# Test_Bench.net
KiCad netlist of a schematic drawn in EAGLE
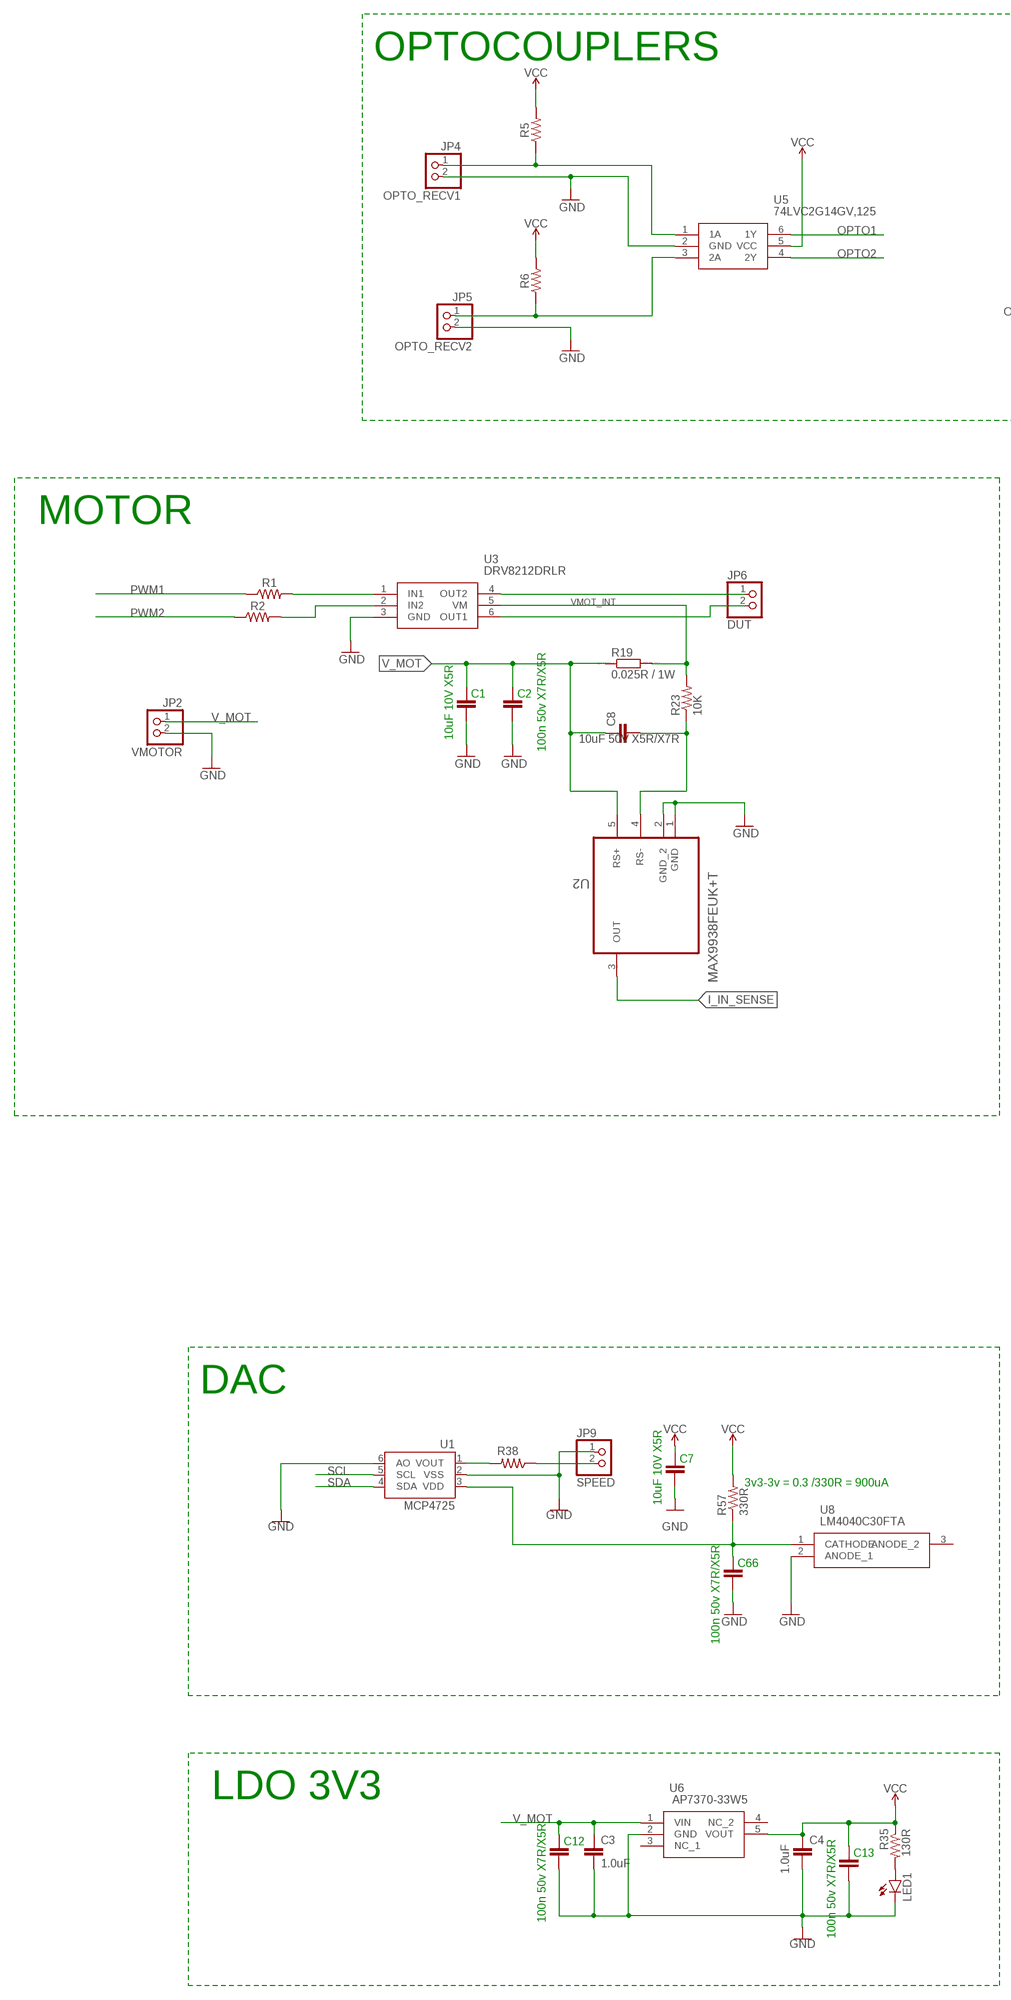
[diagram p0: schematic, sheet 1, part 1 of 2]
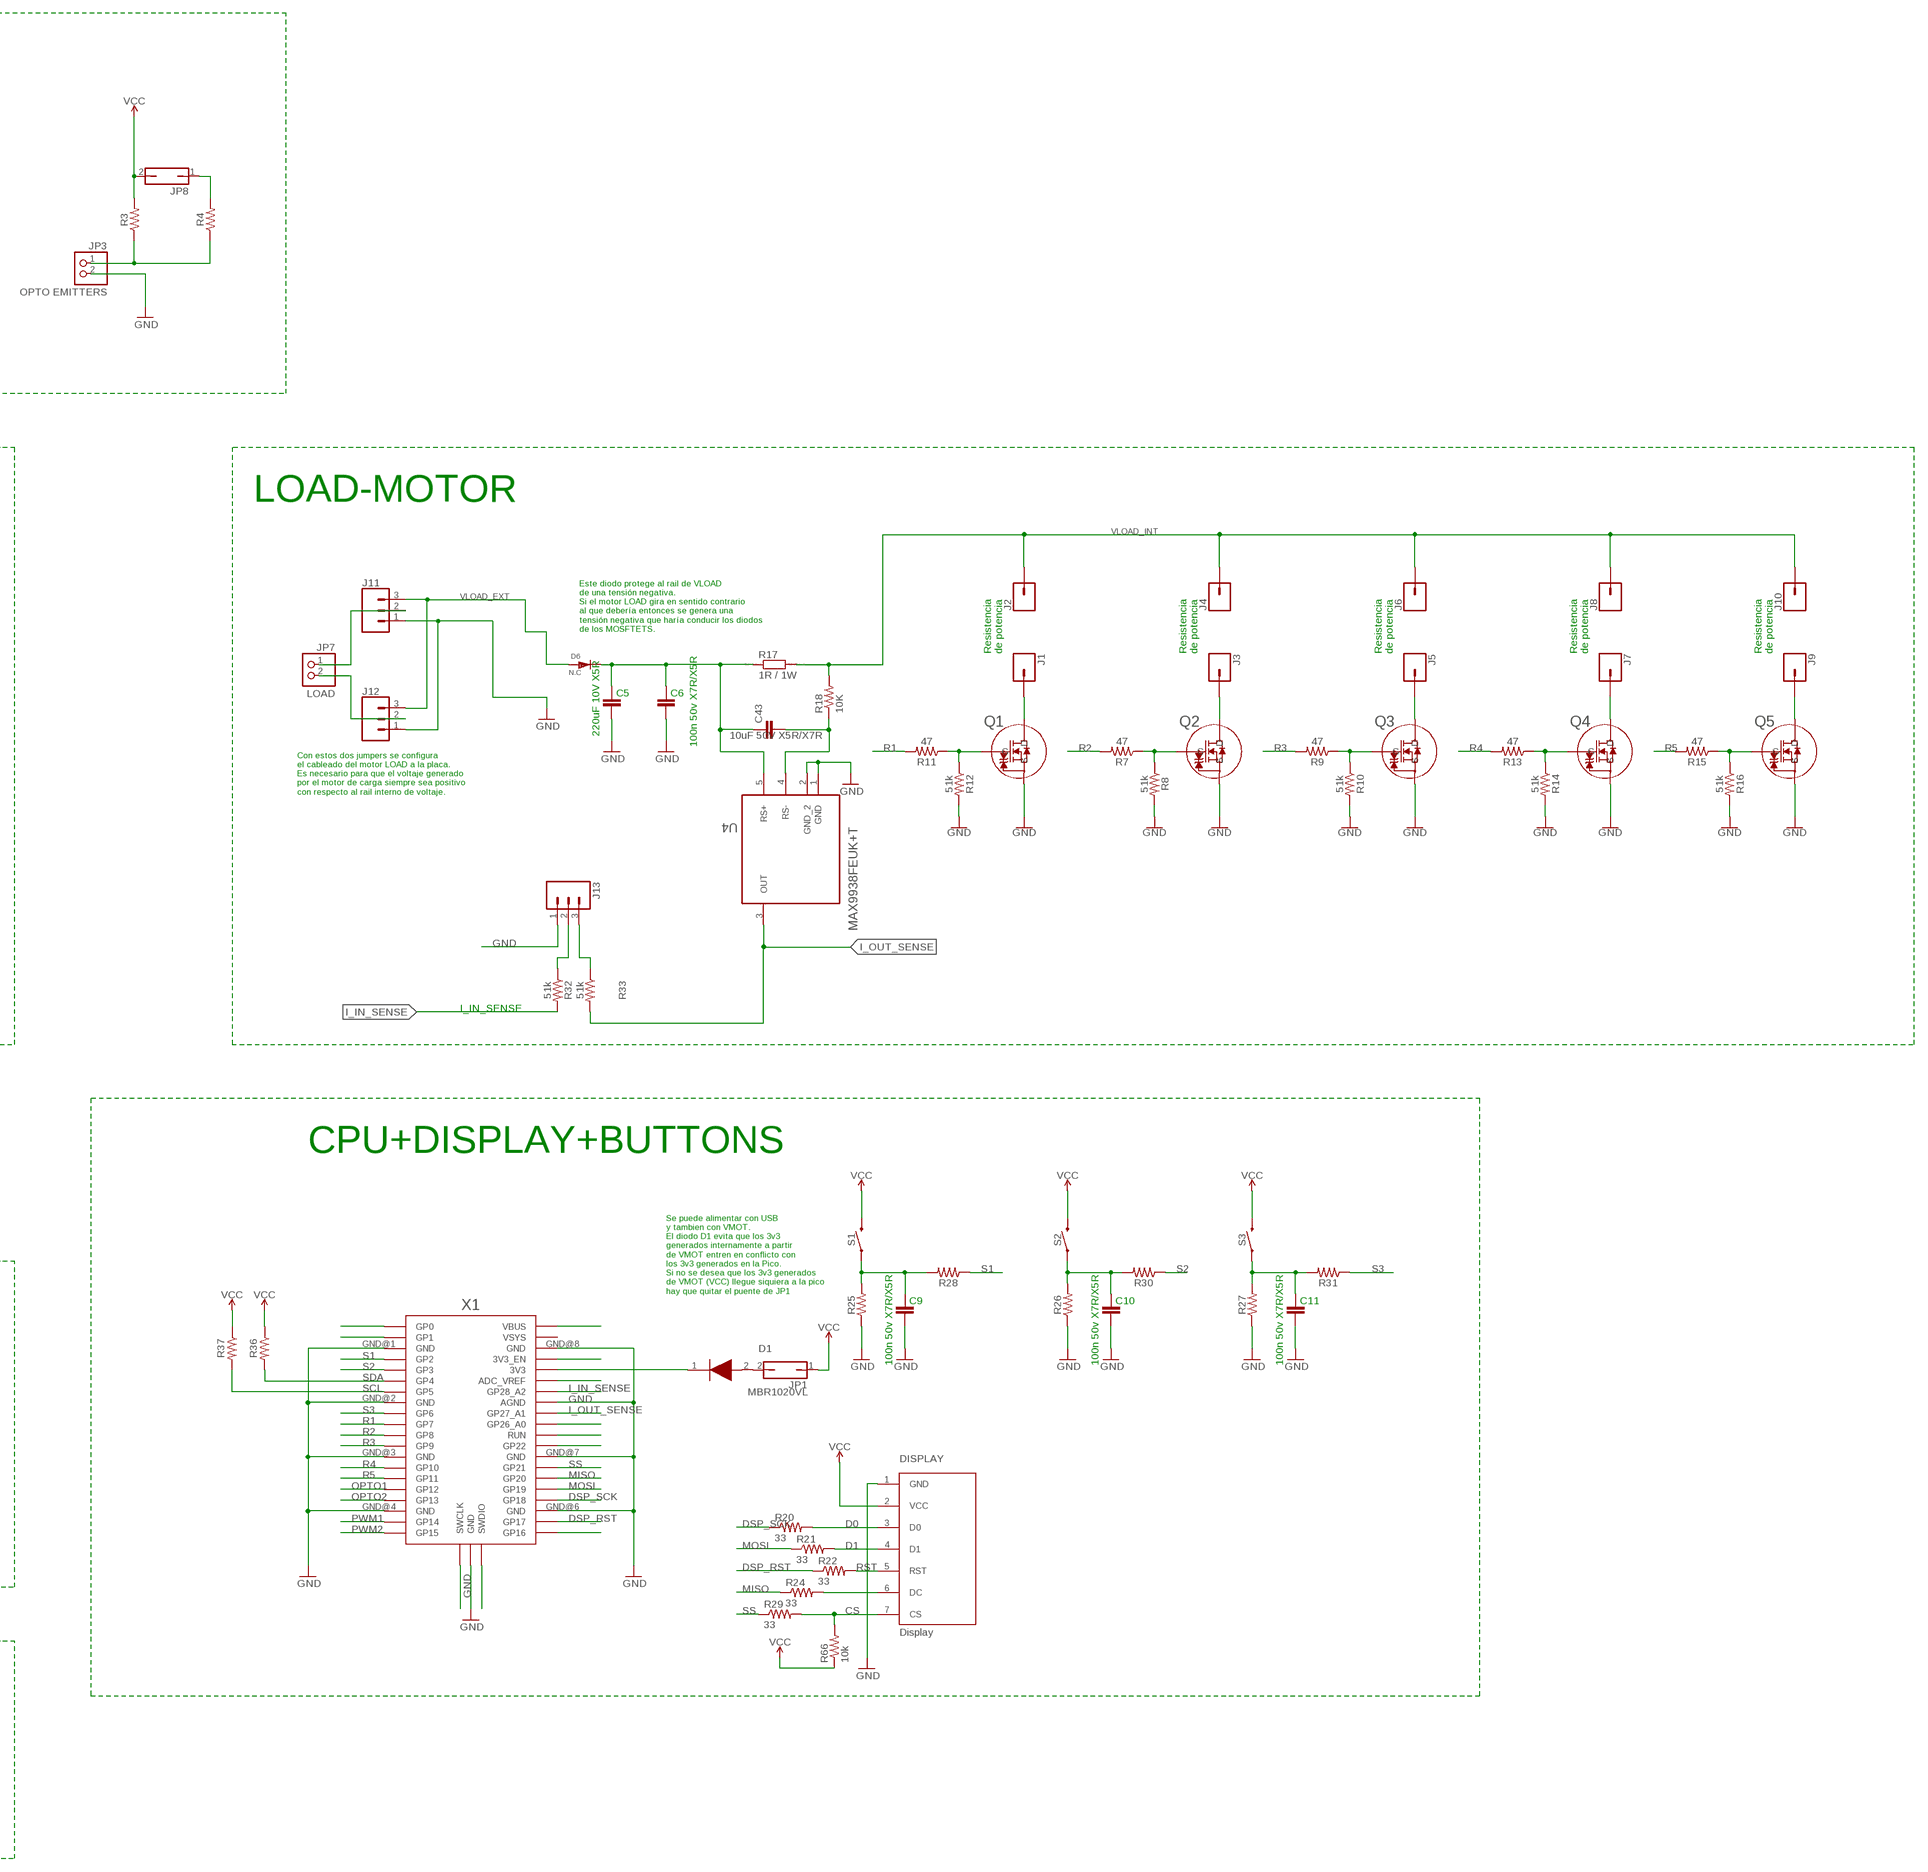
[diagram p1: schematic, sheet 1, part 2 of 2]

(export (version "E")
  (design (tool "Eeschema 10.0.6"))
  (components
    (comp (ref "C1")
      (value "10uF 10V X5R")
      (footprint "eagle-import:0805")
      (libsource (lib "eagle-import") (part "CAP0805"))
    )
    (comp (ref "C2")
      (value "100n 50v X7R/X5R")
      (footprint "eagle-import:0805")
      (libsource (lib "eagle-import") (part "CAP0805"))
    )
    (comp (ref "C3")
      (value "1.0uF")
      (footprint "eagle-import:0805")
      (libsource (lib "eagle-import") (part "1.0UF-0805-25V-(+80/-20%)"))
    )
    (comp (ref "C4")
      (value "1.0uF")
      (footprint "eagle-import:0805")
      (libsource (lib "eagle-import") (part "1.0UF-0805-25V-(+80/-20%)"))
    )
    (comp (ref "C5")
      (value "220uF 10V X5R")
      (footprint "eagle-import:0805")
      (libsource (lib "eagle-import") (part "CAP0805"))
    )
    (comp (ref "C6")
      (value "100n 50v X7R/X5R")
      (footprint "eagle-import:0805")
      (libsource (lib "eagle-import") (part "CAP0805"))
    )
    (comp (ref "C7")
      (value "10uF 10V X5R")
      (footprint "eagle-import:0805")
      (libsource (lib "eagle-import") (part "CAP0805"))
    )
    (comp (ref "C8")
      (value "10uF 50V X5R/X7R")
      (footprint "eagle-import:1206")
      (libsource (lib "eagle-import") (part "CAP1206"))
    )
    (comp (ref "C9")
      (value "100n 50v X7R/X5R")
      (footprint "eagle-import:0805")
      (libsource (lib "eagle-import") (part "CAP0805"))
    )
    (comp (ref "C10")
      (value "100n 50v X7R/X5R")
      (footprint "eagle-import:0805")
      (libsource (lib "eagle-import") (part "CAP0805"))
    )
    (comp (ref "C11")
      (value "100n 50v X7R/X5R")
      (footprint "eagle-import:0805")
      (libsource (lib "eagle-import") (part "CAP0805"))
    )
    (comp (ref "C12")
      (value "100n 50v X7R/X5R")
      (footprint "eagle-import:0805")
      (libsource (lib "eagle-import") (part "CAP0805"))
    )
    (comp (ref "C13")
      (value "100n 50v X7R/X5R")
      (footprint "eagle-import:0805")
      (libsource (lib "eagle-import") (part "CAP0805"))
    )
    (comp (ref "C43")
      (value "10uF 50V X5R/X7R")
      (footprint "eagle-import:1206")
      (libsource (lib "eagle-import") (part "CAP1206"))
    )
    (comp (ref "C66")
      (value "100n 50v X7R/X5R")
      (footprint "eagle-import:0805")
      (libsource (lib "eagle-import") (part "CAP0805"))
    )
    (comp (ref "D1")
      (value "MBR1020VL")
      (footprint "eagle-import:SODFL3617X108N")
      (fields (field (name "MOUSER_PART_NUMBER") "512-MBR1020VL"))
      (libsource (lib "eagle-import") (part "MBR1020VL"))
    )
    (comp (ref "D6")
      (value "N.C")
      (footprint "eagle-import:DO-214AB")
      (libsource (lib "eagle-import") (part "DSMC"))
    )
    (comp (ref "DISPLAY")
      (value "Display")
      (footprint "eagle-import:OLED_LCD")
      (libsource (lib "eagle-import") (part "OLED_LCD"))
    )
    (comp (ref "J1")
      (value "CONN_01")
      (footprint "eagle-import:1X01")
      (libsource (lib "eagle-import") (part "CONN_01"))
    )
    (comp (ref "J2")
      (value "CONN_01")
      (footprint "eagle-import:1X01")
      (libsource (lib "eagle-import") (part "CONN_01"))
    )
    (comp (ref "J3")
      (value "CONN_01")
      (footprint "eagle-import:1X01")
      (libsource (lib "eagle-import") (part "CONN_01"))
    )
    (comp (ref "J4")
      (value "CONN_01")
      (footprint "eagle-import:1X01")
      (libsource (lib "eagle-import") (part "CONN_01"))
    )
    (comp (ref "J5")
      (value "CONN_01")
      (footprint "eagle-import:1X01")
      (libsource (lib "eagle-import") (part "CONN_01"))
    )
    (comp (ref "J6")
      (value "CONN_01")
      (footprint "eagle-import:1X01")
      (libsource (lib "eagle-import") (part "CONN_01"))
    )
    (comp (ref "J7")
      (value "CONN_01")
      (footprint "eagle-import:1X01")
      (libsource (lib "eagle-import") (part "CONN_01"))
    )
    (comp (ref "J8")
      (value "CONN_01")
      (footprint "eagle-import:1X01")
      (libsource (lib "eagle-import") (part "CONN_01"))
    )
    (comp (ref "J9")
      (value "CONN_01")
      (footprint "eagle-import:1X01")
      (libsource (lib "eagle-import") (part "CONN_01"))
    )
    (comp (ref "J10")
      (value "CONN_01")
      (footprint "eagle-import:1X01")
      (libsource (lib "eagle-import") (part "CONN_01"))
    )
    (comp (ref "J11")
      (value "CONN_03")
      (footprint "eagle-import:1X03")
      (libsource (lib "eagle-import") (part "CONN_03"))
    )
    (comp (ref "J12")
      (value "CONN_03")
      (footprint "eagle-import:1X03")
      (libsource (lib "eagle-import") (part "CONN_03"))
    )
    (comp (ref "J13")
      (value "CONN_03")
      (footprint "eagle-import:1X03")
      (libsource (lib "eagle-import") (part "CONN_03"))
    )
    (comp (ref "JP1")
      (value "JP1Q")
      (footprint "eagle-import:JP1")
      (libsource (lib "eagle-import") (part "JP1Q"))
    )
    (comp (ref "JP2")
      (value "VMOTOR")
      (footprint "eagle-import:1X02")
      (fields (field (name "MANUFACTURER") "Generic"))
      (libsource (lib "eagle-import") (part "PINHD-1X2"))
    )
    (comp (ref "JP3")
      (value "OPTO EMITTERS")
      (footprint "eagle-import:1X02")
      (fields (field (name "MANUFACTURER") "Generic"))
      (libsource (lib "eagle-import") (part "PINHD-1X2"))
    )
    (comp (ref "JP4")
      (value "OPTO_RECV1")
      (footprint "eagle-import:1X02")
      (fields (field (name "MANUFACTURER") "Generic"))
      (libsource (lib "eagle-import") (part "PINHD-1X2"))
    )
    (comp (ref "JP5")
      (value "OPTO_RECV2")
      (footprint "eagle-import:1X02")
      (fields (field (name "MANUFACTURER") "Generic"))
      (libsource (lib "eagle-import") (part "PINHD-1X2"))
    )
    (comp (ref "JP6")
      (value "DUT")
      (footprint "eagle-import:1X02")
      (fields (field (name "MANUFACTURER") "Generic"))
      (libsource (lib "eagle-import") (part "PINHD-1X2"))
    )
    (comp (ref "JP7")
      (value "LOAD")
      (footprint "eagle-import:1X02")
      (fields (field (name "MANUFACTURER") "Generic"))
      (libsource (lib "eagle-import") (part "PINHD-1X2"))
    )
    (comp (ref "JP8")
      (value "JP1Q")
      (footprint "eagle-import:JP1")
      (libsource (lib "eagle-import") (part "JP1Q"))
    )
    (comp (ref "JP9")
      (value "SPEED")
      (footprint "eagle-import:1X02")
      (fields (field (name "MANUFACTURER") "Generic"))
      (libsource (lib "eagle-import") (part "PINHD-1X2"))
    )
    (comp (ref "LED1")
      (value "LED3MM")
      (footprint "eagle-import:LED3MM")
      (libsource (lib "eagle-import") (part "LED3MM"))
    )
    (comp (ref "Q1")
      (value "PJA3416AE_R1_00001")
      (footprint "eagle-import:SOT23_PJA3416_PNJ")
      (fields (field (name "COPYRIGHT") "Copyright (C) 2022 Ultra Librarian. All rights reserved."))
      (libsource (lib "eagle-import") (part "PJA3416AE_R1_00001"))
    )
    (comp (ref "Q2")
      (value "PJA3416AE_R1_00001")
      (footprint "eagle-import:SOT23_PJA3416_PNJ")
      (fields (field (name "COPYRIGHT") "Copyright (C) 2022 Ultra Librarian. All rights reserved."))
      (libsource (lib "eagle-import") (part "PJA3416AE_R1_00001"))
    )
    (comp (ref "Q3")
      (value "PJA3416AE_R1_00001")
      (footprint "eagle-import:SOT23_PJA3416_PNJ")
      (fields (field (name "COPYRIGHT") "Copyright (C) 2022 Ultra Librarian. All rights reserved."))
      (libsource (lib "eagle-import") (part "PJA3416AE_R1_00001"))
    )
    (comp (ref "Q4")
      (value "PJA3416AE_R1_00001")
      (footprint "eagle-import:SOT23_PJA3416_PNJ")
      (fields (field (name "COPYRIGHT") "Copyright (C) 2022 Ultra Librarian. All rights reserved."))
      (libsource (lib "eagle-import") (part "PJA3416AE_R1_00001"))
    )
    (comp (ref "Q5")
      (value "PJA3416AE_R1_00001")
      (footprint "eagle-import:SOT23_PJA3416_PNJ")
      (fields (field (name "COPYRIGHT") "Copyright (C) 2022 Ultra Librarian. All rights reserved."))
      (libsource (lib "eagle-import") (part "PJA3416AE_R1_00001"))
    )
    (comp (ref "R1")
      (value "RESISTOR0805")
      (footprint "eagle-import:0805")
      (libsource (lib "eagle-import") (part "RESISTOR0805"))
    )
    (comp (ref "R2")
      (value "RESISTOR0805")
      (footprint "eagle-import:0805")
      (libsource (lib "eagle-import") (part "RESISTOR0805"))
    )
    (comp (ref "R3")
      (value "RESISTOR0805")
      (footprint "eagle-import:0805")
      (libsource (lib "eagle-import") (part "RESISTOR0805"))
    )
    (comp (ref "R4")
      (value "RESISTOR0805")
      (footprint "eagle-import:0805")
      (libsource (lib "eagle-import") (part "RESISTOR0805"))
    )
    (comp (ref "R5")
      (value "RESISTOR0805")
      (footprint "eagle-import:0805")
      (libsource (lib "eagle-import") (part "RESISTOR0805"))
    )
    (comp (ref "R6")
      (value "RESISTOR0805")
      (footprint "eagle-import:0805")
      (libsource (lib "eagle-import") (part "RESISTOR0805"))
    )
    (comp (ref "R7")
      (value "47")
      (footprint "eagle-import:0805")
      (libsource (lib "eagle-import") (part "RESISTOR0805"))
    )
    (comp (ref "R8")
      (value "51k")
      (footprint "eagle-import:0805")
      (libsource (lib "eagle-import") (part "RESISTOR0805"))
    )
    (comp (ref "R9")
      (value "47")
      (footprint "eagle-import:0805")
      (libsource (lib "eagle-import") (part "RESISTOR0805"))
    )
    (comp (ref "R10")
      (value "51k")
      (footprint "eagle-import:0805")
      (libsource (lib "eagle-import") (part "RESISTOR0805"))
    )
    (comp (ref "R11")
      (value "47")
      (footprint "eagle-import:0805")
      (libsource (lib "eagle-import") (part "RESISTOR0805"))
    )
    (comp (ref "R12")
      (value "51k")
      (footprint "eagle-import:0805")
      (libsource (lib "eagle-import") (part "RESISTOR0805"))
    )
    (comp (ref "R13")
      (value "47")
      (footprint "eagle-import:0805")
      (libsource (lib "eagle-import") (part "RESISTOR0805"))
    )
    (comp (ref "R14")
      (value "51k")
      (footprint "eagle-import:0805")
      (libsource (lib "eagle-import") (part "RESISTOR0805"))
    )
    (comp (ref "R15")
      (value "47")
      (footprint "eagle-import:0805")
      (libsource (lib "eagle-import") (part "RESISTOR0805"))
    )
    (comp (ref "R16")
      (value "51k")
      (footprint "eagle-import:0805")
      (libsource (lib "eagle-import") (part "RESISTOR0805"))
    )
    (comp (ref "R17")
      (value "1R / 1W")
      (footprint "eagle-import:R2512")
      (libsource (lib "eagle-import") (part "RR2512"))
    )
    (comp (ref "R18")
      (value "10K")
      (footprint "eagle-import:0805")
      (libsource (lib "eagle-import") (part "RESISTOR0805"))
    )
    (comp (ref "R19")
      (value "0.025R / 1W")
      (footprint "eagle-import:R2512")
      (libsource (lib "eagle-import") (part "RR2512"))
    )
    (comp (ref "R20")
      (value "33")
      (footprint "eagle-import:0805")
      (libsource (lib "eagle-import") (part "RESISTOR0805"))
    )
    (comp (ref "R21")
      (value "33")
      (footprint "eagle-import:0805")
      (libsource (lib "eagle-import") (part "RESISTOR0805"))
    )
    (comp (ref "R22")
      (value "33")
      (footprint "eagle-import:0805")
      (libsource (lib "eagle-import") (part "RESISTOR0805"))
    )
    (comp (ref "R23")
      (value "10K")
      (footprint "eagle-import:0805")
      (libsource (lib "eagle-import") (part "RESISTOR0805"))
    )
    (comp (ref "R24")
      (value "33")
      (footprint "eagle-import:0805")
      (libsource (lib "eagle-import") (part "RESISTOR0805"))
    )
    (comp (ref "R25")
      (value "RESISTOR0805")
      (footprint "eagle-import:0805")
      (libsource (lib "eagle-import") (part "RESISTOR0805"))
    )
    (comp (ref "R26")
      (value "RESISTOR0805")
      (footprint "eagle-import:0805")
      (libsource (lib "eagle-import") (part "RESISTOR0805"))
    )
    (comp (ref "R27")
      (value "RESISTOR0805")
      (footprint "eagle-import:0805")
      (libsource (lib "eagle-import") (part "RESISTOR0805"))
    )
    (comp (ref "R28")
      (value "RESISTOR0805")
      (footprint "eagle-import:0805")
      (libsource (lib "eagle-import") (part "RESISTOR0805"))
    )
    (comp (ref "R29")
      (value "33")
      (footprint "eagle-import:0805")
      (libsource (lib "eagle-import") (part "RESISTOR0805"))
    )
    (comp (ref "R30")
      (value "RESISTOR0805")
      (footprint "eagle-import:0805")
      (libsource (lib "eagle-import") (part "RESISTOR0805"))
    )
    (comp (ref "R31")
      (value "RESISTOR0805")
      (footprint "eagle-import:0805")
      (libsource (lib "eagle-import") (part "RESISTOR0805"))
    )
    (comp (ref "R32")
      (value "51k")
      (footprint "eagle-import:0805")
      (libsource (lib "eagle-import") (part "RESISTOR0805"))
    )
    (comp (ref "R33")
      (value "51k")
      (footprint "eagle-import:0805")
      (libsource (lib "eagle-import") (part "RESISTOR0805"))
    )
    (comp (ref "R35")
      (value "130R")
      (footprint "eagle-import:0805")
      (libsource (lib "eagle-import") (part "RESISTOR0805"))
    )
    (comp (ref "R36")
      (value "RESISTOR0805")
      (footprint "eagle-import:0805")
      (libsource (lib "eagle-import") (part "RESISTOR0805"))
    )
    (comp (ref "R37")
      (value "RESISTOR0805")
      (footprint "eagle-import:0805")
      (libsource (lib "eagle-import") (part "RESISTOR0805"))
    )
    (comp (ref "R38")
      (value "RESISTOR0805")
      (footprint "eagle-import:0805")
      (libsource (lib "eagle-import") (part "RESISTOR0805"))
    )
    (comp (ref "R57")
      (value "330R")
      (footprint "eagle-import:0805")
      (libsource (lib "eagle-import") (part "RESISTOR0805"))
    )
    (comp (ref "R66")
      (value "10k")
      (footprint "eagle-import:0805")
      (libsource (lib "eagle-import") (part "RESISTOR0805"))
    )
    (comp (ref "S1")
      (value "MOMENTARY-SWITCH-SPST-SMD-5.2MM")
      (footprint "eagle-import:TACTILE_SWITCH_SMD_5.2MM")
      (libsource (lib "eagle-import") (part "MOMENTARY-SWITCH-SPST-SMD-5.2MM"))
    )
    (comp (ref "S2")
      (value "MOMENTARY-SWITCH-SPST-SMD-5.2MM")
      (footprint "eagle-import:TACTILE_SWITCH_SMD_5.2MM")
      (libsource (lib "eagle-import") (part "MOMENTARY-SWITCH-SPST-SMD-5.2MM"))
    )
    (comp (ref "S3")
      (value "MOMENTARY-SWITCH-SPST-SMD-5.2MM")
      (footprint "eagle-import:TACTILE_SWITCH_SMD_5.2MM")
      (libsource (lib "eagle-import") (part "MOMENTARY-SWITCH-SPST-SMD-5.2MM"))
    )
    (comp (ref "U1")
      (value "MCP4725")
      (footprint "eagle-import:SOT23-6")
      (libsource (lib "eagle-import") (part "MCP4725SOT-23"))
    )
    (comp (ref "U2")
      (value "MAX9938FEUK+T")
      (footprint "eagle-import:SOT95P280X145-5N")
      (libsource (lib "eagle-import") (part "MAX9938FEUK+T"))
    )
    (comp (ref "U3")
      (value "DRV8212DRLR")
      (footprint "eagle-import:SOTFL50P160X60-6N")
      (fields (field (name "MOUSER_PART_NUMBER") "595-DRV8212DRLR"))
      (libsource (lib "eagle-import") (part "DRV8212DRLR"))
    )
    (comp (ref "U4")
      (value "MAX9938FEUK+T")
      (footprint "eagle-import:SOT95P280X145-5N")
      (libsource (lib "eagle-import") (part "MAX9938FEUK+T"))
    )
    (comp (ref "U5")
      (value "74LVC2G14GV,125")
      (footprint "eagle-import:SOT95P275X110-6N")
      (fields (field (name "MOUSER_PART_NUMBER") "771-LVC2G14GV125"))
      (libsource (lib "eagle-import") (part "74LVC2G14GV,125"))
    )
    (comp (ref "U6")
      (value "AP7370-33W5")
      (footprint "eagle-import:SOT95P285X140-5N")
      (fields
        (field (name "ARROW_PART_NUMBER") "AP7370-50W5-7")
        (field (name "MOUSER_PART_NUMBER") "621-AP7370-50W5-7")
      )
      (libsource (lib "eagle-import") (part "AP7370-50W5-7"))
    )
    (comp (ref "U8")
      (value "LM4040C30FTA")
      (footprint "eagle-import:SOT96P240X120-3N")
      (fields (field (name "MOUSER_PART_NUMBER") "621-LM4040C30FTA"))
      (libsource (lib "eagle-import") (part "LM4040C30FTA"))
    )
    (comp (ref "X1")
      (value "RPI_PICO_IG-TH")
      (footprint "eagle-import:RPI_PICO_TH")
      (libsource (lib "eagle-import") (part "RPI_PICO_IG-TH"))
    )
  )
  (nets
    (net (code "1") (name "/CS") (class "Default")
      (node (ref "DISPLAY") (pin "7") (pinfunction "CS_7") (pintype "bidirectional"))
      (node (ref "R29") (pin "2") (pinfunction "2_2") (pintype "passive"))
      (node (ref "R66") (pin "2") (pinfunction "2_2") (pintype "passive"))
    )
    (net (code "2") (name "/D0") (class "Default")
      (node (ref "DISPLAY") (pin "3") (pinfunction "D0_3") (pintype "bidirectional"))
      (node (ref "R20") (pin "2") (pinfunction "2_2") (pintype "passive"))
    )
    (net (code "3") (name "/D1") (class "Default")
      (node (ref "DISPLAY") (pin "4") (pinfunction "D1_4") (pintype "bidirectional"))
      (node (ref "R21") (pin "2") (pinfunction "2_2") (pintype "passive"))
    )
    (net (code "4") (name "/DSP_RST") (class "Default")
      (node (ref "R22") (pin "1") (pinfunction "1_1") (pintype "passive"))
      (node (ref "X1") (pin "GP17") (pinfunction "GP17_GP17") (pintype "bidirectional"))
    )
    (net (code "5") (name "/DSP_SCK") (class "Default")
      (node (ref "R20") (pin "1") (pinfunction "1_1") (pintype "passive"))
      (node (ref "X1") (pin "GP18") (pinfunction "GP18_GP18") (pintype "bidirectional"))
    )
    (net (code "6") (name "/MISO") (class "Default")
      (node (ref "R24") (pin "1") (pinfunction "1_1") (pintype "passive"))
      (node (ref "X1") (pin "GP20") (pinfunction "GP20_GP20") (pintype "bidirectional"))
    )
    (net (code "7") (name "/MOSI") (class "Default")
      (node (ref "R21") (pin "1") (pinfunction "1_1") (pintype "passive"))
      (node (ref "X1") (pin "GP19") (pinfunction "GP19_GP19") (pintype "bidirectional"))
    )
    (net (code "8") (name "/OPTO1") (class "Default")
      (node (ref "U5") (pin "6") (pinfunction "1Y_6") (pintype "bidirectional"))
      (node (ref "X1") (pin "GP12") (pinfunction "GP12_GP12") (pintype "bidirectional"))
    )
    (net (code "9") (name "/OPTO2") (class "Default")
      (node (ref "U5") (pin "4") (pinfunction "2Y_4") (pintype "bidirectional"))
      (node (ref "X1") (pin "GP13") (pinfunction "GP13_GP13") (pintype "bidirectional"))
    )
    (net (code "10") (name "/PWM1") (class "Default")
      (node (ref "R1") (pin "1") (pinfunction "1_1") (pintype "passive"))
      (node (ref "X1") (pin "GP14") (pinfunction "GP14_GP14") (pintype "bidirectional"))
    )
    (net (code "11") (name "/PWM2") (class "Default")
      (node (ref "R2") (pin "1") (pinfunction "1_1") (pintype "passive"))
      (node (ref "X1") (pin "GP15") (pinfunction "GP15_GP15") (pintype "bidirectional"))
    )
    (net (code "12") (name "/R1") (class "Default")
      (node (ref "R11") (pin "2") (pinfunction "2_2") (pintype "passive"))
      (node (ref "X1") (pin "GP7") (pinfunction "GP7_GP7") (pintype "bidirectional"))
    )
    (net (code "13") (name "/R2") (class "Default")
      (node (ref "R7") (pin "2") (pinfunction "2_2") (pintype "passive"))
      (node (ref "X1") (pin "GP8") (pinfunction "GP8_GP8") (pintype "bidirectional"))
    )
    (net (code "14") (name "/R3") (class "Default")
      (node (ref "R9") (pin "2") (pinfunction "2_2") (pintype "passive"))
      (node (ref "X1") (pin "GP9") (pinfunction "GP9_GP9") (pintype "bidirectional"))
    )
    (net (code "15") (name "/R4") (class "Default")
      (node (ref "R13") (pin "2") (pinfunction "2_2") (pintype "passive"))
      (node (ref "X1") (pin "GP10") (pinfunction "GP10_GP10") (pintype "bidirectional"))
    )
    (net (code "16") (name "/R5") (class "Default")
      (node (ref "R15") (pin "2") (pinfunction "2_2") (pintype "passive"))
      (node (ref "X1") (pin "GP11") (pinfunction "GP11_GP11") (pintype "bidirectional"))
    )
    (net (code "17") (name "/RST") (class "Default")
      (node (ref "DISPLAY") (pin "5") (pinfunction "RST_5") (pintype "bidirectional"))
      (node (ref "R22") (pin "2") (pinfunction "2_2") (pintype "passive"))
    )
    (net (code "18") (name "/S1") (class "Default")
      (node (ref "R28") (pin "1") (pinfunction "1_1") (pintype "passive"))
      (node (ref "X1") (pin "GP2") (pinfunction "GP2_GP2") (pintype "bidirectional"))
    )
    (net (code "19") (name "/S2") (class "Default")
      (node (ref "R30") (pin "1") (pinfunction "1_1") (pintype "passive"))
      (node (ref "X1") (pin "GP3") (pinfunction "GP3_GP3") (pintype "bidirectional"))
    )
    (net (code "20") (name "/S3") (class "Default")
      (node (ref "R31") (pin "1") (pinfunction "1_1") (pintype "passive"))
      (node (ref "X1") (pin "GP6") (pinfunction "GP6_GP6") (pintype "bidirectional"))
    )
    (net (code "21") (name "/SCL") (class "Default")
      (node (ref "R37") (pin "2") (pinfunction "2_2") (pintype "passive"))
      (node (ref "U1") (pin "5") (pinfunction "SCL_5") (pintype "bidirectional"))
      (node (ref "X1") (pin "GP5") (pinfunction "GP5_GP5") (pintype "bidirectional"))
    )
    (net (code "22") (name "/SDA") (class "Default")
      (node (ref "R36") (pin "2") (pinfunction "2_2") (pintype "passive"))
      (node (ref "U1") (pin "4") (pinfunction "SDA_4") (pintype "bidirectional"))
      (node (ref "X1") (pin "GP4") (pinfunction "GP4_GP4") (pintype "bidirectional"))
    )
    (net (code "23") (name "/SS") (class "Default")
      (node (ref "R29") (pin "1") (pinfunction "1_1") (pintype "passive"))
      (node (ref "X1") (pin "GP21") (pinfunction "GP21_GP21") (pintype "bidirectional"))
    )
    (net (code "24") (name "/VLOAD_EXT") (class "Default")
      (node (ref "D6") (pin "1") (pinfunction "A_1") (pintype "bidirectional"))
      (node (ref "J11") (pin "3") (pinfunction "3_3") (pintype "passive"))
      (node (ref "J12") (pin "3") (pinfunction "3_3") (pintype "passive"))
    )
    (net (code "25") (name "/VLOAD_INT") (class "Default")
      (node (ref "J10") (pin "1") (pinfunction "1_1") (pintype "passive"))
      (node (ref "J2") (pin "1") (pinfunction "1_1") (pintype "passive"))
      (node (ref "J4") (pin "1") (pinfunction "1_1") (pintype "passive"))
      (node (ref "J6") (pin "1") (pinfunction "1_1") (pintype "passive"))
      (node (ref "J8") (pin "1") (pinfunction "1_1") (pintype "passive"))
      (node (ref "R17") (pin "2") (pinfunction "2_2") (pintype "passive"))
      (node (ref "R18") (pin "2") (pinfunction "2_2") (pintype "passive"))
    )
    (net (code "26") (name "/VMOT_INT") (class "Default")
      (node (ref "R19") (pin "2") (pinfunction "2_2") (pintype "passive"))
      (node (ref "R23") (pin "2") (pinfunction "2_2") (pintype "passive"))
      (node (ref "U3") (pin "5") (pinfunction "VM_5") (pintype "bidirectional"))
    )
    (net (code "27") (name "GND") (class "Default")
      (node (ref "C1") (pin "1") (pinfunction "1_1") (pintype "passive"))
      (node (ref "C10") (pin "1") (pinfunction "1_1") (pintype "passive"))
      (node (ref "C11") (pin "1") (pinfunction "1_1") (pintype "passive"))
      (node (ref "C12") (pin "1") (pinfunction "1_1") (pintype "passive"))
      (node (ref "C13") (pin "1") (pinfunction "1_1") (pintype "passive"))
      (node (ref "C2") (pin "1") (pinfunction "1_1") (pintype "passive"))
      (node (ref "C3") (pin "2") (pinfunction "2_2") (pintype "passive"))
      (node (ref "C4") (pin "2") (pinfunction "2_2") (pintype "passive"))
      (node (ref "C5") (pin "1") (pinfunction "1_1") (pintype "passive"))
      (node (ref "C6") (pin "1") (pinfunction "1_1") (pintype "passive"))
      (node (ref "C66") (pin "1") (pinfunction "1_1") (pintype "passive"))
      (node (ref "C7") (pin "1") (pinfunction "1_1") (pintype "passive"))
      (node (ref "C9") (pin "1") (pinfunction "1_1") (pintype "passive"))
      (node (ref "DISPLAY") (pin "1") (pinfunction "GND_1") (pintype "bidirectional"))
      (node (ref "J11") (pin "1") (pinfunction "1_1") (pintype "passive"))
      (node (ref "J12") (pin "1") (pinfunction "1_1") (pintype "passive"))
      (node (ref "J13") (pin "1") (pinfunction "1_1") (pintype "passive"))
      (node (ref "JP2") (pin "2") (pinfunction "2_2") (pintype "passive"))
      (node (ref "JP3") (pin "2") (pinfunction "2_2") (pintype "passive"))
      (node (ref "JP4") (pin "2") (pinfunction "2_2") (pintype "passive"))
      (node (ref "JP5") (pin "2") (pinfunction "2_2") (pintype "passive"))
      (node (ref "JP9") (pin "1") (pinfunction "1_1") (pintype "passive"))
      (node (ref "LED1") (pin "K") (pinfunction "C_K") (pintype "passive"))
      (node (ref "Q1") (pin "2") (pinfunction "S_2") (pintype "passive"))
      (node (ref "Q2") (pin "2") (pinfunction "S_2") (pintype "passive"))
      (node (ref "Q3") (pin "2") (pinfunction "S_2") (pintype "passive"))
      (node (ref "Q4") (pin "2") (pinfunction "S_2") (pintype "passive"))
      (node (ref "Q5") (pin "2") (pinfunction "S_2") (pintype "passive"))
      (node (ref "R10") (pin "2") (pinfunction "2_2") (pintype "passive"))
      (node (ref "R12") (pin "2") (pinfunction "2_2") (pintype "passive"))
      (node (ref "R14") (pin "2") (pinfunction "2_2") (pintype "passive"))
      (node (ref "R16") (pin "2") (pinfunction "2_2") (pintype "passive"))
      (node (ref "R25") (pin "1") (pinfunction "1_1") (pintype "passive"))
      (node (ref "R26") (pin "1") (pinfunction "1_1") (pintype "passive"))
      (node (ref "R27") (pin "1") (pinfunction "1_1") (pintype "passive"))
      (node (ref "R8") (pin "2") (pinfunction "2_2") (pintype "passive"))
      (node (ref "U1") (pin "2") (pinfunction "VSS_2") (pintype "bidirectional"))
      (node (ref "U1") (pin "6") (pinfunction "AO_6") (pintype "bidirectional"))
      (node (ref "U2") (pin "1") (pinfunction "GND_1") (pintype "passive"))
      (node (ref "U2") (pin "2") (pinfunction "GND_2_2") (pintype "passive"))
      (node (ref "U3") (pin "3") (pinfunction "GND_3") (pintype "bidirectional"))
      (node (ref "U4") (pin "1") (pinfunction "GND_1") (pintype "passive"))
      (node (ref "U4") (pin "2") (pinfunction "GND_2_2") (pintype "passive"))
      (node (ref "U5") (pin "2") (pinfunction "GND_2") (pintype "bidirectional"))
      (node (ref "U6") (pin "2") (pinfunction "GND_2") (pintype "bidirectional"))
      (node (ref "U8") (pin "2") (pinfunction "ANODE_1_2") (pintype "bidirectional"))
      (node (ref "X1") (pin "AGND") (pinfunction "AGND_AGND") (pintype "bidirectional"))
      (node (ref "X1") (pin "GND@1") (pinfunction "GND_GND@1") (pintype "bidirectional"))
      (node (ref "X1") (pin "GND@2") (pinfunction "GND_GND@2") (pintype "bidirectional"))
      (node (ref "X1") (pin "GND@3") (pinfunction "GND_GND@3") (pintype "bidirectional"))
      (node (ref "X1") (pin "GND@4") (pinfunction "GND_GND@4") (pintype "bidirectional"))
      (node (ref "X1") (pin "GND@5") (pinfunction "GND_GND@5") (pintype "bidirectional"))
      (node (ref "X1") (pin "GND@6") (pinfunction "GND_GND@6") (pintype "bidirectional"))
      (node (ref "X1") (pin "GND@7") (pinfunction "GND_GND@7") (pintype "bidirectional"))
      (node (ref "X1") (pin "GND@8") (pinfunction "GND_GND@8") (pintype "bidirectional"))
    )
    (net (code "28") (name "I_IN_SENSE") (class "Default")
      (node (ref "R32") (pin "2") (pinfunction "2_2") (pintype "passive"))
      (node (ref "U2") (pin "3") (pinfunction "OUT_3") (pintype "output"))
      (node (ref "X1") (pin "GP28_A2") (pinfunction "GP28_A2_GP28_A2") (pintype "bidirectional"))
    )
    (net (code "29") (name "I_OUT_SENSE") (class "Default")
      (node (ref "R33") (pin "2") (pinfunction "2_2") (pintype "passive"))
      (node (ref "U4") (pin "3") (pinfunction "OUT_3") (pintype "output"))
      (node (ref "X1") (pin "GP27_A1") (pinfunction "GP27_A1_GP27_A1") (pintype "bidirectional"))
    )
    (net (code "30") (name "Net-(C9-Pad2)") (class "Default")
      (node (ref "C9") (pin "2") (pinfunction "2_2") (pintype "passive"))
      (node (ref "R25") (pin "2") (pinfunction "2_2") (pintype "passive"))
      (node (ref "R28") (pin "2") (pinfunction "2_2") (pintype "passive"))
      (node (ref "S1") (pin "1") (pinfunction "1_1") (pintype "passive"))
    )
    (net (code "31") (name "Net-(C10-Pad2)") (class "Default")
      (node (ref "C10") (pin "2") (pinfunction "2_2") (pintype "passive"))
      (node (ref "R26") (pin "2") (pinfunction "2_2") (pintype "passive"))
      (node (ref "R30") (pin "2") (pinfunction "2_2") (pintype "passive"))
      (node (ref "S2") (pin "1") (pinfunction "1_1") (pintype "passive"))
    )
    (net (code "32") (name "Net-(C11-Pad2)") (class "Default")
      (node (ref "C11") (pin "2") (pinfunction "2_2") (pintype "passive"))
      (node (ref "R27") (pin "2") (pinfunction "2_2") (pintype "passive"))
      (node (ref "R31") (pin "2") (pinfunction "2_2") (pintype "passive"))
      (node (ref "S3") (pin "1") (pinfunction "1_1") (pintype "passive"))
    )
    (net (code "33") (name "Net-(D1-A)") (class "Default")
      (node (ref "D1") (pin "2") (pinfunction "A_2") (pintype "bidirectional"))
      (node (ref "JP1") (pin "2") (pinfunction "2_2") (pintype "passive"))
    )
    (net (code "34") (name "Net-(D1-K)") (class "Default")
      (node (ref "D1") (pin "1") (pinfunction "K_1") (pintype "bidirectional"))
      (node (ref "X1") (pin "3V3") (pinfunction "3V3_3V3") (pintype "bidirectional"))
    )
    (net (code "35") (name "Net-(D6-K)") (class "Default")
      (node (ref "C43") (pin "1") (pinfunction "1_1") (pintype "passive"))
      (node (ref "C5") (pin "2") (pinfunction "2_2") (pintype "passive"))
      (node (ref "C6") (pin "2") (pinfunction "2_2") (pintype "passive"))
      (node (ref "D6") (pin "2") (pinfunction "K_2") (pintype "bidirectional"))
      (node (ref "R17") (pin "1") (pinfunction "1_1") (pintype "passive"))
      (node (ref "U4") (pin "5") (pinfunction "RS+_5") (pintype "power_in"))
    )
    (net (code "36") (name "Net-(DISPLAY-DC)") (class "Default")
      (node (ref "DISPLAY") (pin "6") (pinfunction "DC_6") (pintype "bidirectional"))
      (node (ref "R24") (pin "2") (pinfunction "2_2") (pintype "passive"))
    )
    (net (code "37") (name "Net-(J11-Pad2)") (class "Default")
      (node (ref "J11") (pin "2") (pinfunction "2_2") (pintype "passive"))
      (node (ref "JP7") (pin "1") (pinfunction "1_1") (pintype "passive"))
    )
    (net (code "38") (name "Net-(J12-Pad2)") (class "Default")
      (node (ref "J12") (pin "2") (pinfunction "2_2") (pintype "passive"))
      (node (ref "JP7") (pin "2") (pinfunction "2_2") (pintype "passive"))
    )
    (net (code "39") (name "Net-(J13-Pad2)") (class "Default")
      (node (ref "J13") (pin "2") (pinfunction "2_2") (pintype "passive"))
      (node (ref "R32") (pin "1") (pinfunction "1_1") (pintype "passive"))
    )
    (net (code "40") (name "Net-(J13-Pad3)") (class "Default")
      (node (ref "J13") (pin "3") (pinfunction "3_3") (pintype "passive"))
      (node (ref "R33") (pin "1") (pinfunction "1_1") (pintype "passive"))
    )
    (net (code "41") (name "Net-(JP3-Pad1)") (class "Default")
      (node (ref "JP3") (pin "1") (pinfunction "1_1") (pintype "passive"))
      (node (ref "R3") (pin "1") (pinfunction "1_1") (pintype "passive"))
      (node (ref "R4") (pin "1") (pinfunction "1_1") (pintype "passive"))
    )
    (net (code "42") (name "Net-(JP8-Pad1)") (class "Default")
      (node (ref "JP8") (pin "1") (pinfunction "1_1") (pintype "passive"))
      (node (ref "R4") (pin "2") (pinfunction "2_2") (pintype "passive"))
    )
    (net (code "43") (name "Net-(JP9-Pad2)") (class "Default")
      (node (ref "JP9") (pin "2") (pinfunction "2_2") (pintype "passive"))
      (node (ref "R38") (pin "1") (pinfunction "1_1") (pintype "passive"))
    )
    (net (code "44") (name "Net-(LED1-PadA)") (class "Default")
      (node (ref "LED1") (pin "A") (pinfunction "A_A") (pintype "passive"))
      (node (ref "R35") (pin "2") (pinfunction "2_2") (pintype "passive"))
    )
    (net (code "45") (name "Net-(Q1-D)") (class "Default")
      (node (ref "J1") (pin "1") (pinfunction "1_1") (pintype "passive"))
      (node (ref "Q1") (pin "3") (pinfunction "D_3") (pintype "passive"))
    )
    (net (code "46") (name "Net-(Q1-G)") (class "Default")
      (node (ref "Q1") (pin "1") (pinfunction "G_1") (pintype "passive"))
      (node (ref "R11") (pin "1") (pinfunction "1_1") (pintype "passive"))
      (node (ref "R12") (pin "1") (pinfunction "1_1") (pintype "passive"))
    )
    (net (code "47") (name "Net-(Q2-D)") (class "Default")
      (node (ref "J3") (pin "1") (pinfunction "1_1") (pintype "passive"))
      (node (ref "Q2") (pin "3") (pinfunction "D_3") (pintype "passive"))
    )
    (net (code "48") (name "Net-(Q2-G)") (class "Default")
      (node (ref "Q2") (pin "1") (pinfunction "G_1") (pintype "passive"))
      (node (ref "R7") (pin "1") (pinfunction "1_1") (pintype "passive"))
      (node (ref "R8") (pin "1") (pinfunction "1_1") (pintype "passive"))
    )
    (net (code "49") (name "Net-(Q3-D)") (class "Default")
      (node (ref "J5") (pin "1") (pinfunction "1_1") (pintype "passive"))
      (node (ref "Q3") (pin "3") (pinfunction "D_3") (pintype "passive"))
    )
    (net (code "50") (name "Net-(Q3-G)") (class "Default")
      (node (ref "Q3") (pin "1") (pinfunction "G_1") (pintype "passive"))
      (node (ref "R10") (pin "1") (pinfunction "1_1") (pintype "passive"))
      (node (ref "R9") (pin "1") (pinfunction "1_1") (pintype "passive"))
    )
    (net (code "51") (name "Net-(Q4-D)") (class "Default")
      (node (ref "J7") (pin "1") (pinfunction "1_1") (pintype "passive"))
      (node (ref "Q4") (pin "3") (pinfunction "D_3") (pintype "passive"))
    )
    (net (code "52") (name "Net-(Q4-G)") (class "Default")
      (node (ref "Q4") (pin "1") (pinfunction "G_1") (pintype "passive"))
      (node (ref "R13") (pin "1") (pinfunction "1_1") (pintype "passive"))
      (node (ref "R14") (pin "1") (pinfunction "1_1") (pintype "passive"))
    )
    (net (code "53") (name "Net-(Q5-D)") (class "Default")
      (node (ref "J9") (pin "1") (pinfunction "1_1") (pintype "passive"))
      (node (ref "Q5") (pin "3") (pinfunction "D_3") (pintype "passive"))
    )
    (net (code "54") (name "Net-(Q5-G)") (class "Default")
      (node (ref "Q5") (pin "1") (pinfunction "G_1") (pintype "passive"))
      (node (ref "R15") (pin "1") (pinfunction "1_1") (pintype "passive"))
      (node (ref "R16") (pin "1") (pinfunction "1_1") (pintype "passive"))
    )
    (net (code "55") (name "Net-(U1-VDD)") (class "Default")
      (node (ref "C66") (pin "2") (pinfunction "2_2") (pintype "passive"))
      (node (ref "R57") (pin "1") (pinfunction "1_1") (pintype "passive"))
      (node (ref "U1") (pin "3") (pinfunction "VDD_3") (pintype "bidirectional"))
      (node (ref "U8") (pin "1") (pinfunction "CATHODE_1") (pintype "bidirectional"))
    )
    (net (code "56") (name "Net-(U1-VOUT)") (class "Default")
      (node (ref "R38") (pin "2") (pinfunction "2_2") (pintype "passive"))
      (node (ref "U1") (pin "1") (pinfunction "VOUT_1") (pintype "bidirectional"))
    )
    (net (code "57") (name "Net-(U2-RS-)") (class "Default")
      (node (ref "C8") (pin "2") (pinfunction "2_2") (pintype "passive"))
      (node (ref "R23") (pin "1") (pinfunction "1_1") (pintype "passive"))
      (node (ref "U2") (pin "4") (pinfunction "RS-_4") (pintype "input"))
    )
    (net (code "58") (name "Net-(U3-IN1)") (class "Default")
      (node (ref "R1") (pin "2") (pinfunction "2_2") (pintype "passive"))
      (node (ref "U3") (pin "1") (pinfunction "IN1_1") (pintype "bidirectional"))
    )
    (net (code "59") (name "Net-(U3-IN2)") (class "Default")
      (node (ref "R2") (pin "2") (pinfunction "2_2") (pintype "passive"))
      (node (ref "U3") (pin "2") (pinfunction "IN2_2") (pintype "bidirectional"))
    )
    (net (code "60") (name "Net-(U3-OUT1)") (class "Default")
      (node (ref "JP6") (pin "2") (pinfunction "2_2") (pintype "passive"))
      (node (ref "U3") (pin "6") (pinfunction "OUT1_6") (pintype "bidirectional"))
    )
    (net (code "61") (name "Net-(U3-OUT2)") (class "Default")
      (node (ref "JP6") (pin "1") (pinfunction "1_1") (pintype "passive"))
      (node (ref "U3") (pin "4") (pinfunction "OUT2_4") (pintype "bidirectional"))
    )
    (net (code "62") (name "Net-(U4-RS-)") (class "Default")
      (node (ref "C43") (pin "2") (pinfunction "2_2") (pintype "passive"))
      (node (ref "R18") (pin "1") (pinfunction "1_1") (pintype "passive"))
      (node (ref "U4") (pin "4") (pinfunction "RS-_4") (pintype "input"))
    )
    (net (code "63") (name "Net-(U5-1A)") (class "Default")
      (node (ref "JP4") (pin "1") (pinfunction "1_1") (pintype "passive"))
      (node (ref "R5") (pin "1") (pinfunction "1_1") (pintype "passive"))
      (node (ref "U5") (pin "1") (pinfunction "1A_1") (pintype "bidirectional"))
    )
    (net (code "64") (name "Net-(U5-2A)") (class "Default")
      (node (ref "JP5") (pin "1") (pinfunction "1_1") (pintype "passive"))
      (node (ref "R6") (pin "1") (pinfunction "1_1") (pintype "passive"))
      (node (ref "U5") (pin "3") (pinfunction "2A_3") (pintype "bidirectional"))
    )
    (net (code "65") (name "VCC") (class "Default")
      (node (ref "C13") (pin "2") (pinfunction "2_2") (pintype "passive"))
      (node (ref "C4") (pin "1") (pinfunction "1_1") (pintype "passive"))
      (node (ref "C7") (pin "2") (pinfunction "2_2") (pintype "passive"))
      (node (ref "DISPLAY") (pin "2") (pinfunction "VCC_2") (pintype "bidirectional"))
      (node (ref "JP1") (pin "1") (pinfunction "1_1") (pintype "passive"))
      (node (ref "JP8") (pin "2") (pinfunction "2_2") (pintype "passive"))
      (node (ref "R3") (pin "2") (pinfunction "2_2") (pintype "passive"))
      (node (ref "R35") (pin "1") (pinfunction "1_1") (pintype "passive"))
      (node (ref "R36") (pin "1") (pinfunction "1_1") (pintype "passive"))
      (node (ref "R37") (pin "1") (pinfunction "1_1") (pintype "passive"))
      (node (ref "R5") (pin "2") (pinfunction "2_2") (pintype "passive"))
      (node (ref "R57") (pin "2") (pinfunction "2_2") (pintype "passive"))
      (node (ref "R6") (pin "2") (pinfunction "2_2") (pintype "passive"))
      (node (ref "R66") (pin "1") (pinfunction "1_1") (pintype "passive"))
      (node (ref "S1") (pin "3") (pinfunction "2_3") (pintype "passive"))
      (node (ref "S2") (pin "3") (pinfunction "2_3") (pintype "passive"))
      (node (ref "S3") (pin "3") (pinfunction "2_3") (pintype "passive"))
      (node (ref "U5") (pin "5") (pinfunction "VCC_5") (pintype "bidirectional"))
      (node (ref "U6") (pin "5") (pinfunction "VOUT_5") (pintype "bidirectional"))
    )
    (net (code "66") (name "V_MOT") (class "Default")
      (node (ref "C1") (pin "2") (pinfunction "2_2") (pintype "passive"))
      (node (ref "C12") (pin "2") (pinfunction "2_2") (pintype "passive"))
      (node (ref "C2") (pin "2") (pinfunction "2_2") (pintype "passive"))
      (node (ref "C3") (pin "1") (pinfunction "1_1") (pintype "passive"))
      (node (ref "C8") (pin "1") (pinfunction "1_1") (pintype "passive"))
      (node (ref "JP2") (pin "1") (pinfunction "1_1") (pintype "passive"))
      (node (ref "R19") (pin "1") (pinfunction "1_1") (pintype "passive"))
      (node (ref "U2") (pin "5") (pinfunction "RS+_5") (pintype "power_in"))
      (node (ref "U6") (pin "1") (pinfunction "VIN_1") (pintype "bidirectional"))
    )
    (net (code "67") (name "unconnected-(U6-NC_1-Pad3)") (class "Default")
      (node (ref "U6") (pin "3") (pinfunction "NC_1_3") (pintype "bidirectional"))
    )
    (net (code "68") (name "unconnected-(U6-NC_2-Pad4)") (class "Default")
      (node (ref "U6") (pin "4") (pinfunction "NC_2_4") (pintype "bidirectional"))
    )
    (net (code "69") (name "unconnected-(U8-ANODE_2-Pad3)") (class "Default")
      (node (ref "U8") (pin "3") (pinfunction "ANODE_2_3") (pintype "bidirectional"))
    )
    (net (code "70") (name "unconnected-(X1-Pad3V3_EN)") (class "Default")
      (node (ref "X1") (pin "3V3_EN") (pinfunction "3V3_EN_3V3_EN") (pintype "bidirectional"))
    )
    (net (code "71") (name "unconnected-(X1-PadADC_VREF)") (class "Default")
      (node (ref "X1") (pin "ADC_VREF") (pinfunction "ADC_VREF_ADC_VREF") (pintype "bidirectional"))
    )
    (net (code "72") (name "unconnected-(X1-PadGP0)") (class "Default")
      (node (ref "X1") (pin "GP0") (pinfunction "GP0_GP0") (pintype "bidirectional"))
    )
    (net (code "73") (name "unconnected-(X1-PadGP1)") (class "Default")
      (node (ref "X1") (pin "GP1") (pinfunction "GP1_GP1") (pintype "bidirectional"))
    )
    (net (code "74") (name "unconnected-(X1-PadGP16)") (class "Default")
      (node (ref "X1") (pin "GP16") (pinfunction "GP16_GP16") (pintype "bidirectional"))
    )
    (net (code "75") (name "unconnected-(X1-PadGP22)") (class "Default")
      (node (ref "X1") (pin "GP22") (pinfunction "GP22_GP22") (pintype "bidirectional"))
    )
    (net (code "76") (name "unconnected-(X1-PadGP26_A0)") (class "Default")
      (node (ref "X1") (pin "GP26_A0") (pinfunction "GP26_A0_GP26_A0") (pintype "bidirectional"))
    )
    (net (code "77") (name "unconnected-(X1-PadRUN)") (class "Default")
      (node (ref "X1") (pin "RUN") (pinfunction "RUN_RUN") (pintype "bidirectional"))
    )
    (net (code "78") (name "unconnected-(X1-PadSWCLK)") (class "Default")
      (node (ref "X1") (pin "SWCLK") (pinfunction "SWCLK_SWCLK") (pintype "bidirectional"))
    )
    (net (code "79") (name "unconnected-(X1-PadSWDIO)") (class "Default")
      (node (ref "X1") (pin "SWDIO") (pinfunction "SWDIO_SWDIO") (pintype "bidirectional"))
    )
    (net (code "80") (name "unconnected-(X1-PadVBUS)") (class "Default")
      (node (ref "X1") (pin "VBUS") (pinfunction "VBUS_VBUS") (pintype "bidirectional"))
    )
    (net (code "81") (name "unconnected-(X1-PadVSYS)") (class "Default")
      (node (ref "X1") (pin "VSYS") (pinfunction "VSYS_VSYS") (pintype "bidirectional"))
    )
  )
)
